# LCD_ULTRA.net
KiCad netlist of a schematic drawn in Altium Designer
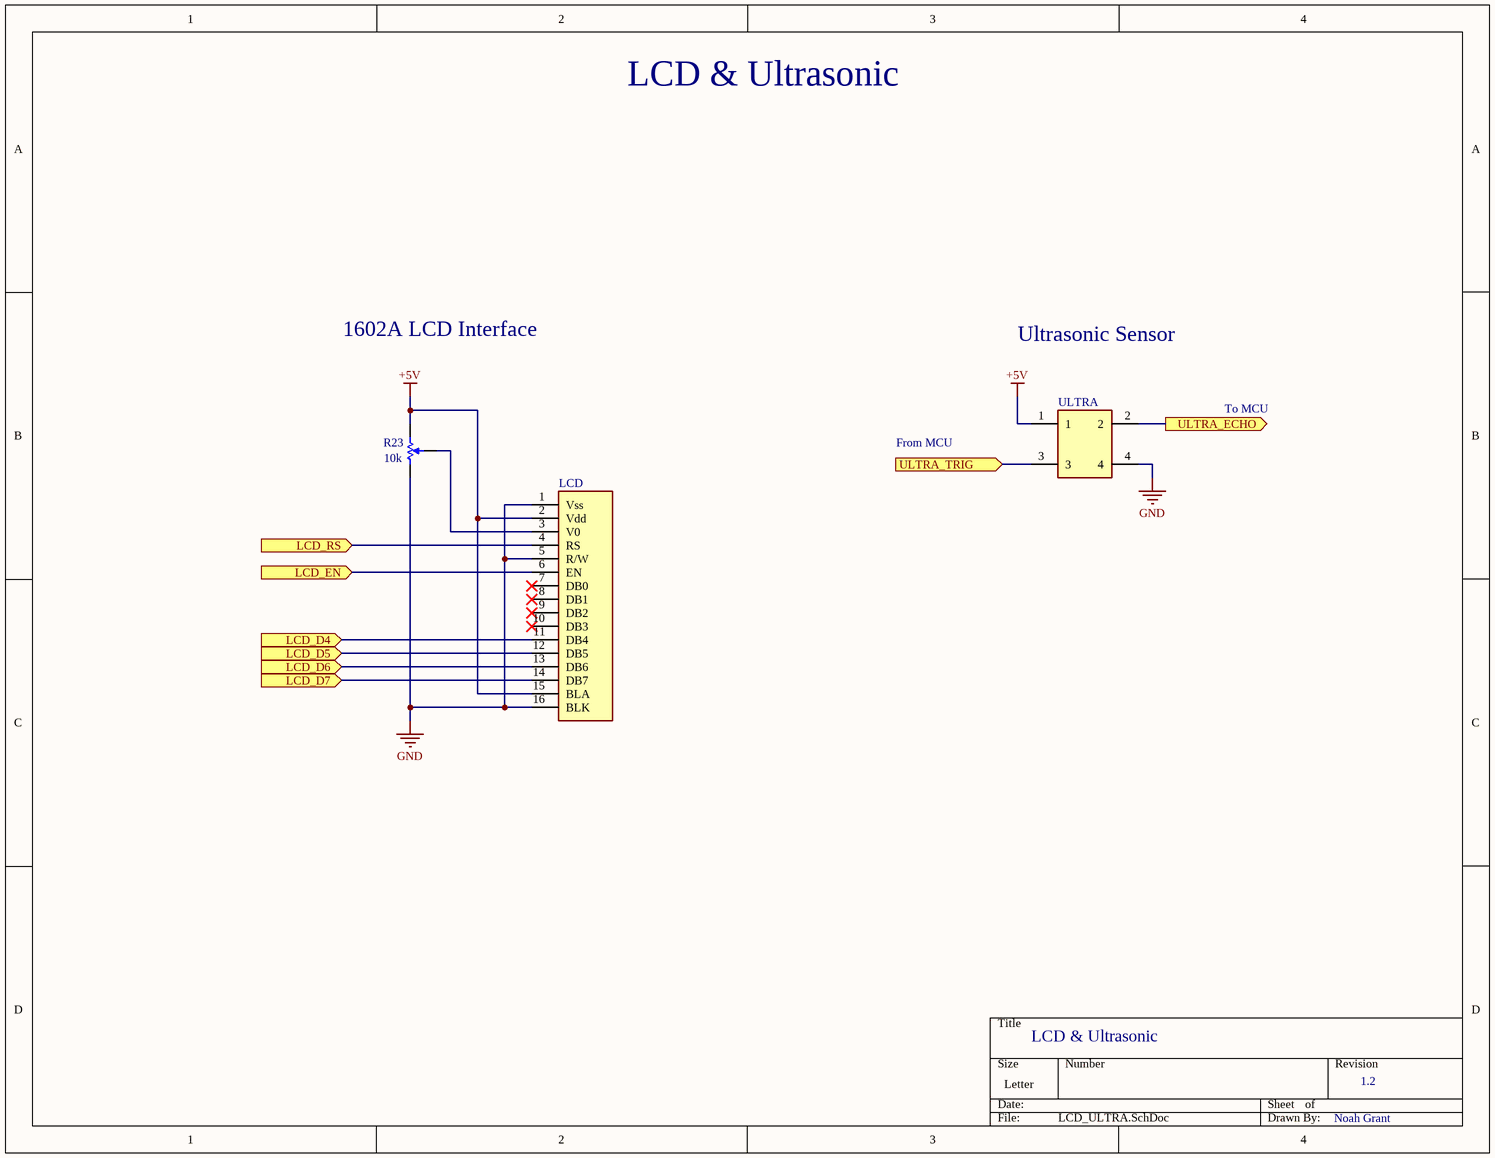
[diagram p0: LCD_ULTRA.SchDoc]

(export (version "E")
  (design (tool "Eeschema 10.0.6"))
  (components
    (comp (ref "LCD")
      (value "PPPC161LFBN-RC")
      (footprint "SamacSys:RHDR16W80P0X254_1X16_4114X254X850P")
      (description "Connector")
      (libsource (lib "*") (part "PPPC161LFBN-RC"))
    )
    (comp (ref "R23")
      (value "10k")
      (footprint "BOUR-TC33X-2_V")
      (description "Trimming Potentiometer, 10000 Ohm, -40 to 100 degC, 3-Pin SMD, RoHS, Tape and Reel")
      (fields (field (name "TOLERANCE") "25%") (field (name "MANUFACTURER") "Bourns"))
      (libsource (lib "Altium Content Vault") (part "RES-ADJ-3_A"))
    )
    (comp (ref "ULTRA")
      (value "22-28-4043")
      (footprint "SamacSys:HDRV4W87P0X254_1X4_1016X249X863P")
      (description "Connector")
      (fields (field (name "MOUSER PART NUMBER") "538-22-28-4043"))
      (libsource (lib "*") (part "22-28-4043"))
    )
  )
  (nets
    (net (code "1") (name "+5V") (class "Default")
      (node (ref "LCD") (pin "15") (pinfunction "BLA_15") (pintype "passive"))
      (node (ref "LCD") (pin "2") (pinfunction "Vdd_2") (pintype "passive"))
      (node (ref "R23") (pin "3") (pinfunction "3_3") (pintype "passive"))
      (node (ref "ULTRA") (pin "1") (pinfunction "1_1") (pintype "passive"))
    )
    (net (code "2") (name "/LCD_D4") (class "Default")
      (node (ref "LCD") (pin "11") (pinfunction "DB4_11") (pintype "passive"))
    )
    (net (code "3") (name "/LCD_D5") (class "Default")
      (node (ref "LCD") (pin "12") (pinfunction "DB5_12") (pintype "passive"))
    )
    (net (code "4") (name "/LCD_D6") (class "Default")
      (node (ref "LCD") (pin "13") (pinfunction "DB6_13") (pintype "passive"))
    )
    (net (code "5") (name "/LCD_D7") (class "Default")
      (node (ref "LCD") (pin "14") (pinfunction "DB7_14") (pintype "passive"))
    )
    (net (code "6") (name "/LCD_EN") (class "Default")
      (node (ref "LCD") (pin "6") (pinfunction "EN_6") (pintype "passive"))
    )
    (net (code "7") (name "/LCD_RS") (class "Default")
      (node (ref "LCD") (pin "4") (pinfunction "RS_4") (pintype "passive"))
    )
    (net (code "8") (name "/ULTRA_ECHO") (class "Default")
      (node (ref "ULTRA") (pin "2") (pinfunction "2_2") (pintype "passive"))
    )
    (net (code "9") (name "/ULTRA_TRIG") (class "Default")
      (node (ref "ULTRA") (pin "3") (pinfunction "3_3") (pintype "passive"))
    )
    (net (code "10") (name "GND") (class "Default")
      (node (ref "LCD") (pin "1") (pinfunction "Vss_1") (pintype "passive"))
      (node (ref "LCD") (pin "16") (pinfunction "BLK_16") (pintype "passive"))
      (node (ref "LCD") (pin "5") (pinfunction "R/W_5") (pintype "passive"))
      (node (ref "R23") (pin "1") (pinfunction "1_1") (pintype "passive"))
      (node (ref "ULTRA") (pin "4") (pinfunction "4_4") (pintype "passive"))
    )
    (net (code "11") (name "Net-(LCD-V0)") (class "Default")
      (node (ref "LCD") (pin "3") (pinfunction "V0_3") (pintype "passive"))
      (node (ref "R23") (pin "2") (pinfunction "2_2") (pintype "passive"))
    )
    (net (code "12") (name "unconnected-(LCD-DB0-Pad7)") (class "Default")
      (node (ref "LCD") (pin "7") (pinfunction "DB0_7") (pintype "passive+no_connect"))
    )
    (net (code "13") (name "unconnected-(LCD-DB1-Pad8)") (class "Default")
      (node (ref "LCD") (pin "8") (pinfunction "DB1_8") (pintype "passive+no_connect"))
    )
    (net (code "14") (name "unconnected-(LCD-DB2-Pad9)") (class "Default")
      (node (ref "LCD") (pin "9") (pinfunction "DB2_9") (pintype "passive+no_connect"))
    )
    (net (code "15") (name "unconnected-(LCD-DB3-Pad10)") (class "Default")
      (node (ref "LCD") (pin "10") (pinfunction "DB3_10") (pintype "passive+no_connect"))
    )
  )
)
